# mcu.net
KiCad netlist of a schematic drawn in Altium Designer
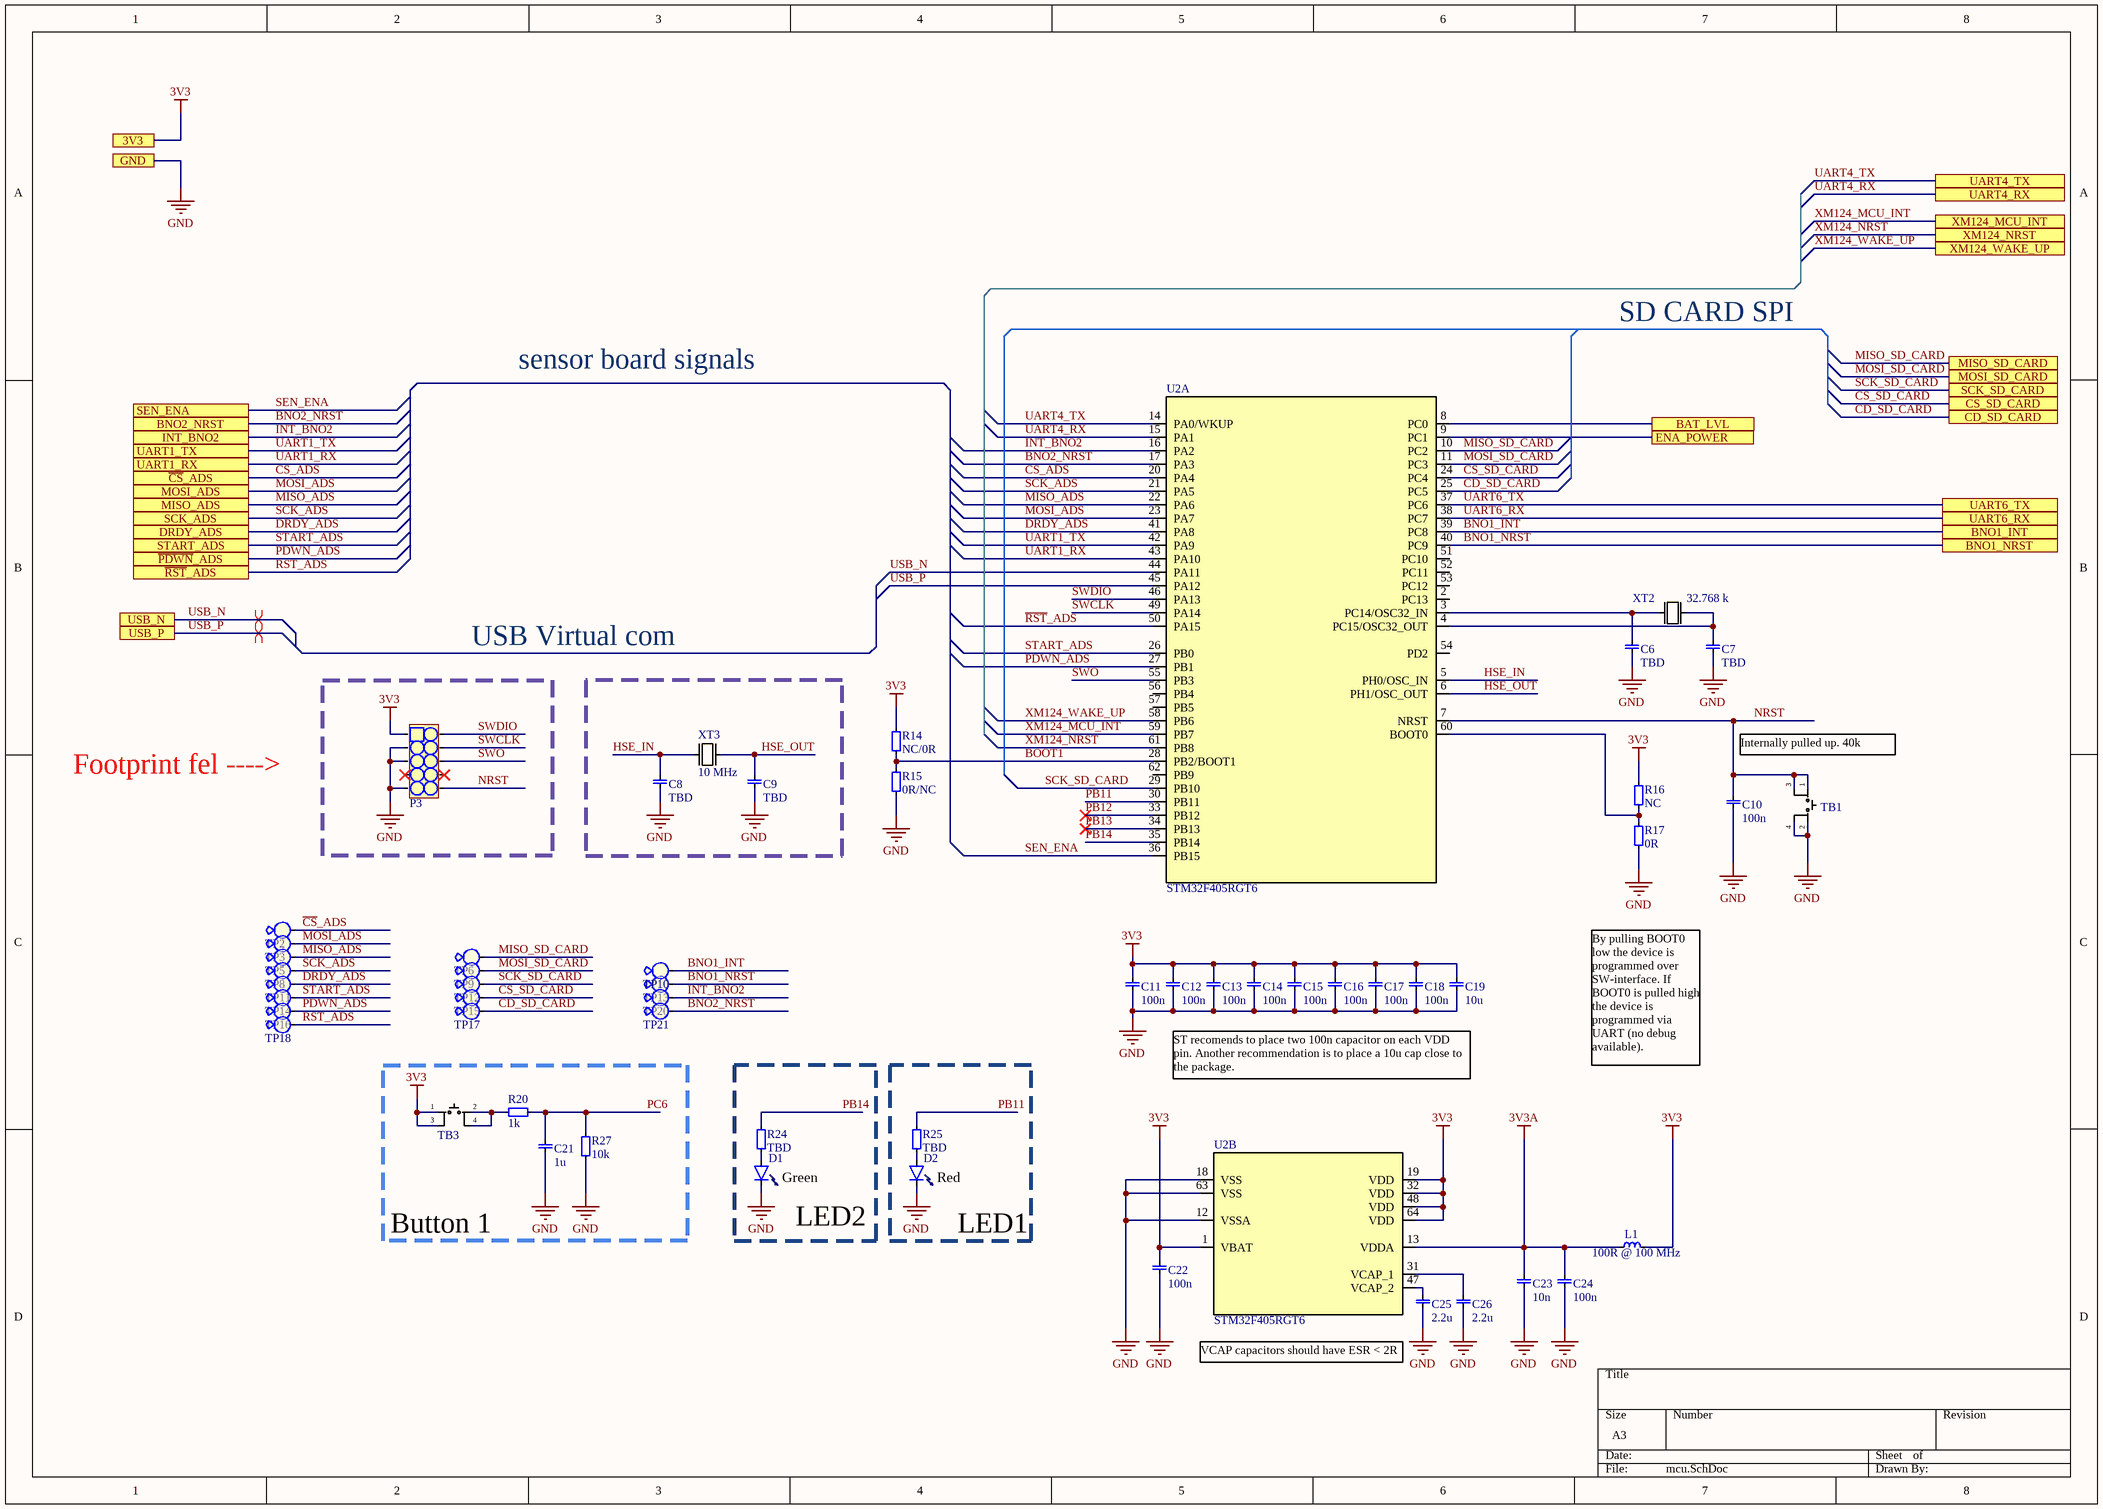
[diagram p0: mcu.SchDoc]

(export (version "E")
  (design (tool "Eeschema 10.0.6"))
  (components
    (comp (ref "C6")
      (value "TBD")
      (footprint "0603 cap")
      (fields (field (name "Comment") "0603, capacitor"))
      (libsource (lib "jclib") (part "0603, capacitor"))
    )
    (comp (ref "C7")
      (value "TBD")
      (footprint "0603 cap")
      (fields (field (name "Comment") "0603, capacitor"))
      (libsource (lib "jclib") (part "0603, capacitor"))
    )
    (comp (ref "C8")
      (value "TBD")
      (footprint "0603 cap")
      (fields (field (name "Comment") "0603, capacitor"))
      (libsource (lib "jclib") (part "0603, capacitor"))
    )
    (comp (ref "C9")
      (value "TBD")
      (footprint "0603 cap")
      (fields (field (name "Comment") "0603, capacitor"))
      (libsource (lib "jclib") (part "0603, capacitor"))
    )
    (comp (ref "C10")
      (value "100n")
      (footprint "0402 CAP")
      (fields
        (field (name "MANUFACTURER PART NO") "GRM155R62A104KE14D")
        (field (name "Comment") "0603, capacitor")
      )
      (libsource (lib "jclib") (part "0603, capacitor"))
    )
    (comp (ref "C11")
      (value "100n")
      (footprint "0402 CAP")
      (fields
        (field (name "MANUFACTURER PART NO") "GRM155R62A104KE14D")
        (field (name "Comment") "0603, capacitor")
      )
      (libsource (lib "jclib") (part "0603, capacitor"))
    )
    (comp (ref "C12")
      (value "100n")
      (footprint "0402 CAP")
      (fields
        (field (name "MANUFACTURER PART NO") "GRM155R62A104KE14D")
        (field (name "Comment") "0603, capacitor")
      )
      (libsource (lib "jclib") (part "0603, capacitor"))
    )
    (comp (ref "C13")
      (value "100n")
      (footprint "0402 CAP")
      (fields
        (field (name "MANUFACTURER PART NO") "GRM155R62A104KE14D")
        (field (name "Comment") "0603, capacitor")
      )
      (libsource (lib "jclib") (part "0603, capacitor"))
    )
    (comp (ref "C14")
      (value "100n")
      (footprint "0402 CAP")
      (fields
        (field (name "MANUFACTURER PART NO") "GRM155R62A104KE14D")
        (field (name "Comment") "0603, capacitor")
      )
      (libsource (lib "jclib") (part "0603, capacitor"))
    )
    (comp (ref "C15")
      (value "100n")
      (footprint "0402 CAP")
      (fields
        (field (name "MANUFACTURER PART NO") "GRM155R62A104KE14D")
        (field (name "Comment") "0603, capacitor")
      )
      (libsource (lib "jclib") (part "0603, capacitor"))
    )
    (comp (ref "C16")
      (value "100n")
      (footprint "0402 CAP")
      (fields
        (field (name "MANUFACTURER PART NO") "GRM155R62A104KE14D")
        (field (name "Comment") "0603, capacitor")
      )
      (libsource (lib "jclib") (part "0603, capacitor"))
    )
    (comp (ref "C17")
      (value "100n")
      (footprint "0402 CAP")
      (fields
        (field (name "MANUFACTURER PART NO") "GRM155R62A104KE14D")
        (field (name "Comment") "0603, capacitor")
      )
      (libsource (lib "jclib") (part "0603, capacitor"))
    )
    (comp (ref "C18")
      (value "100n")
      (footprint "0402 CAP")
      (fields
        (field (name "MANUFACTURER PART NO") "GRM155R62A104KE14D")
        (field (name "Comment") "0603, capacitor")
      )
      (libsource (lib "jclib") (part "0603, capacitor"))
    )
    (comp (ref "C19")
      (value "10u")
      (footprint "0402 CAP")
      (fields
        (field (name "MANUFACTURER PART NO") "GRM155R61A106ME11D")
        (field (name "Comment") "0603, capacitor")
      )
      (libsource (lib "jclib") (part "0603, capacitor"))
    )
    (comp (ref "C21")
      (value "1u")
      (footprint "0402 CAP")
      (fields
        (field (name "MANUFACTURER PART NO") "C0402C105K9PAC7867")
        (field (name "Comment") "0603, capacitor")
      )
      (libsource (lib "jclib") (part "0603, capacitor"))
    )
    (comp (ref "C22")
      (value "100n")
      (footprint "0402 CAP")
      (fields
        (field (name "MANUFACTURER PART NO") "GRM155R62A104KE14D")
        (field (name "Comment") "0603, capacitor")
      )
      (libsource (lib "jclib") (part "0603, capacitor"))
    )
    (comp (ref "C23")
      (value "10n")
      (footprint "0402 CAP")
      (fields
        (field (name "MANUFACTURER PART NO") "CC0402KRX7R0BB103")
        (field (name "Comment") "0603, capacitor")
      )
      (libsource (lib "jclib") (part "0603, capacitor"))
    )
    (comp (ref "C24")
      (value "100n")
      (footprint "0402 CAP")
      (fields
        (field (name "MANUFACTURER PART NO") "GRM155R62A104KE14D")
        (field (name "Comment") "0603, capacitor")
      )
      (libsource (lib "jclib") (part "0603, capacitor"))
    )
    (comp (ref "C25")
      (value "2.2u")
      (footprint "0402 CAP")
      (fields
        (field (name "MANUFACTURER PART NO") "GRM155D71A225ME15D")
        (field (name "Comment") "0603, capacitor")
      )
      (libsource (lib "jclib") (part "0603, capacitor"))
    )
    (comp (ref "C26")
      (value "2.2u")
      (footprint "0402 CAP")
      (fields
        (field (name "MANUFACTURER PART NO") "GRM155D71A225ME15D")
        (field (name "Comment") "0603, capacitor")
      )
      (libsource (lib "jclib") (part "0603, capacitor"))
    )
    (comp (ref "D1")
      (value "0603, LED")
      (footprint "0603 LED")
      (fields (field (name "MANUFACTURER PART NO") "5988081107F"))
      (libsource (lib "jclib") (part "0603, LED"))
    )
    (comp (ref "D2")
      (value "0603, LED")
      (footprint "0603 LED")
      (fields (field (name "MANUFACTURER PART NO") "150060SS75003"))
      (libsource (lib "jclib") (part "0603, LED"))
    )
    (comp (ref "L1")
      (value "100R @ 100 MHz")
      (footprint "0805")
      (fields (field (name "MANUFACTURER PART NO") "74279207") (field (name "Comment") "0805, Ferrite Bead"))
      (libsource (lib "jclib") (part "0805, Ferrite Bead"))
    )
    (comp (ref "P3")
      (value "ARM 10 pin SWD")
      (footprint "FTSH-105-01-L-DV-K even odd")
      (description "1.27mm, PH")
      (fields (field (name "MANUFACTURER PART NO") "FTSH-105-01-L-DV-K"))
      (libsource (lib "jclib") (part "ARM 10 pin SWD"))
    )
    (comp (ref "R14")
      (value "NC/0R")
      (footprint "0402 res")
      (fields
        (field (name "MANUFACTURER PART NO") "RMCF0402ZT0R00")
        (field (name "Comment") "0603, resistor")
      )
      (libsource (lib "jclib") (part "0603, resistor"))
    )
    (comp (ref "R15")
      (value "0R/NC")
      (footprint "0402 res")
      (fields
        (field (name "MANUFACTURER PART NO") "RMCF0402ZT0R00")
        (field (name "Comment") "0603, resistor")
      )
      (libsource (lib "jclib") (part "0603, resistor"))
    )
    (comp (ref "R16")
      (value "NC")
      (footprint "0402 res")
      (fields (field (name "Comment") "0603, resistor"))
      (libsource (lib "jclib") (part "0603, resistor"))
    )
    (comp (ref "R17")
      (value "0R")
      (footprint "0402 res")
      (fields
        (field (name "MANUFACTURER PART NO") "RMCF0402ZT0R00")
        (field (name "Comment") "0603, resistor")
      )
      (libsource (lib "jclib") (part "0603, resistor"))
    )
    (comp (ref "R20")
      (value "1k")
      (footprint "0402 res")
      (fields
        (field (name "MANUFACTURER PART NO") "RC0402FR-071KL")
        (field (name "Comment") "0603, resistor")
      )
      (libsource (lib "jclib") (part "0603, resistor"))
    )
    (comp (ref "R24")
      (value "TBD")
      (footprint "0402 res")
      (fields (field (name "Comment") "0603, resistor"))
      (libsource (lib "jclib") (part "0603, resistor"))
    )
    (comp (ref "R25")
      (value "TBD")
      (footprint "0402 res")
      (fields (field (name "Comment") "0603, resistor"))
      (libsource (lib "jclib") (part "0603, resistor"))
    )
    (comp (ref "R27")
      (value "10k")
      (footprint "0402 res")
      (fields
        (field (name "MANUFACTURER PART NO") "311-10.0KLRCT-ND")
        (field (name "Comment") "0603, resistor")
      )
      (libsource (lib "jclib") (part "0603, resistor"))
    )
    (comp (ref "TB1")
      (value "Tactile Button")
      (footprint "tacButton smd")
      (description "Tactile Switch Small Low")
      (fields (field (name "MANUFACTURER PART NO") "430182043816"))
      (libsource (lib "jclib") (part "TacButton SMD"))
    )
    (comp (ref "TB3")
      (value "Tactile Button")
      (footprint "tacButton smd")
      (description "Tactile Switch Small Low")
      (fields (field (name "MANUFACTURER PART NO") "430182043816"))
      (libsource (lib "jclib") (part "TacButton SMD"))
    )
    (comp (ref "TP2")
      (value "Test Point")
      (footprint "testPoint")
      (libsource (lib "jclib") (part "Test Point"))
    )
    (comp (ref "TP3")
      (value "Test Point")
      (footprint "testPoint")
      (libsource (lib "jclib") (part "Test Point"))
    )
    (comp (ref "TP5")
      (value "Test Point")
      (footprint "testPoint")
      (libsource (lib "jclib") (part "Test Point"))
    )
    (comp (ref "TP6")
      (value "Test Point")
      (footprint "testPoint")
      (libsource (lib "jclib") (part "Test Point"))
    )
    (comp (ref "TP8")
      (value "Test Point")
      (footprint "testPoint")
      (libsource (lib "jclib") (part "Test Point"))
    )
    (comp (ref "TP9")
      (value "Test Point")
      (footprint "testPoint")
      (libsource (lib "jclib") (part "Test Point"))
    )
    (comp (ref "TP10")
      (value "Test Point")
      (footprint "testPoint")
      (libsource (lib "jclib") (part "Test Point"))
    )
    (comp (ref "TP11")
      (value "Test Point")
      (footprint "testPoint")
      (libsource (lib "jclib") (part "Test Point"))
    )
    (comp (ref "TP12")
      (value "Test Point")
      (footprint "testPoint")
      (libsource (lib "jclib") (part "Test Point"))
    )
    (comp (ref "TP13")
      (value "Test Point")
      (footprint "testPoint")
      (libsource (lib "jclib") (part "Test Point"))
    )
    (comp (ref "TP14")
      (value "Test Point")
      (footprint "testPoint")
      (libsource (lib "jclib") (part "Test Point"))
    )
    (comp (ref "TP15")
      (value "Test Point")
      (footprint "testPoint")
      (libsource (lib "jclib") (part "Test Point"))
    )
    (comp (ref "TP16")
      (value "Test Point")
      (footprint "testPoint")
      (libsource (lib "jclib") (part "Test Point"))
    )
    (comp (ref "TP17")
      (value "Test Point")
      (footprint "testPoint")
      (libsource (lib "jclib") (part "Test Point"))
    )
    (comp (ref "TP18")
      (value "Test Point")
      (footprint "testPoint")
      (libsource (lib "jclib") (part "Test Point"))
    )
    (comp (ref "TP20")
      (value "Test Point")
      (footprint "testPoint")
      (libsource (lib "jclib") (part "Test Point"))
    )
    (comp (ref "TP21")
      (value "Test Point")
      (footprint "testPoint")
      (libsource (lib "jclib") (part "Test Point"))
    )
    (comp (ref "U2")
      (value "STM32F405RGT6")
      (footprint "LQFP64-10x10mm_s")
      (description "No Description Available")
      (fields (field (name "COPYRIGHT") "Copyright (C) 2018 Accelerated Designs. All rights reserved"))
      (libsource (lib "jclib") (part "STM32F405RGT6"))
    )
    (comp (ref "XT2")
      (value "32.768 k")
      (footprint "ECS-.327-12.5-39-TR")
      (fields
        (field (name "MANUFACTURER PART NO") "CC4V-T1A-32.768KHZ-9PF-20PPM-TA-QC")
        (field (name "Comment") "Crystal")
      )
      (libsource (lib "jclib") (part "Crystal"))
    )
    (comp (ref "XT3")
      (value "10 MHz")
      (footprint "XTAL_SMD_LP")
      (description "16 MHz, SMD, 5mm x 3,2mm, 30 ppm")
      (fields (field (name "MANUFACTURER PART NO") "7A-10.000MAAJ-T") (field (name "Comment") "XTAL TXC 7A"))
      (libsource (lib "jclib") (part "XTAL TXC 7A"))
    )
  )
  (nets
    (net (code "1") (name "/BAT_LVL") (class "Default")
      (node (ref "U2") (pin "8") (pinfunction "PC0_8") (pintype "passive"))
    )
    (net (code "2") (name "/BNO1_INT") (class "Default")
      (node (ref "TP10") (pin "0") (pinfunction "0_0") (pintype "passive"))
      (node (ref "U2") (pin "39") (pinfunction "PC8_39") (pintype "passive"))
    )
    (net (code "3") (name "/BNO1_NRST") (class "Default")
      (node (ref "TP13") (pin "0") (pinfunction "0_0") (pintype "passive"))
      (node (ref "U2") (pin "40") (pinfunction "PC9_40") (pintype "passive"))
    )
    (net (code "4") (name "/BNO2_NRST") (class "Default")
      (node (ref "TP21") (pin "0") (pinfunction "0_0") (pintype "passive"))
      (node (ref "U2") (pin "17") (pinfunction "PA3_17") (pintype "passive"))
    )
    (net (code "5") (name "/BOOT1") (class "Default")
      (node (ref "R14") (pin "1") (pinfunction "1_1") (pintype "passive"))
      (node (ref "R15") (pin "0") (pinfunction "0_0") (pintype "passive"))
      (node (ref "U2") (pin "28") (pinfunction "PB2/BOOT1_28") (pintype "passive"))
    )
    (net (code "6") (name "/CD_SD_CARD") (class "Default")
      (node (ref "TP17") (pin "0") (pinfunction "0_0") (pintype "passive"))
      (node (ref "U2") (pin "25") (pinfunction "PC5_25") (pintype "passive"))
    )
    (net (code "7") (name "/CS_SD_CARD") (class "Default")
      (node (ref "TP15") (pin "0") (pinfunction "0_0") (pintype "passive"))
      (node (ref "U2") (pin "24") (pinfunction "PC4_24") (pintype "passive"))
    )
    (net (code "8") (name "/DRDY_ADS") (class "Default")
      (node (ref "TP11") (pin "0") (pinfunction "0_0") (pintype "passive"))
      (node (ref "U2") (pin "41") (pinfunction "PA8_41") (pintype "passive"))
    )
    (net (code "9") (name "/ENA_POWER") (class "Default")
      (node (ref "U2") (pin "9") (pinfunction "PC1_9") (pintype "passive"))
    )
    (net (code "10") (name "/HSE_IN") (class "Default")
      (node (ref "C8") (pin "1") (pinfunction "1_1") (pintype "passive"))
      (node (ref "U2") (pin "5") (pinfunction "PH0/OSC_IN_5") (pintype "passive"))
      (node (ref "XT3") (pin "1") (pinfunction "1_1") (pintype "passive"))
    )
    (net (code "11") (name "/HSE_OUT") (class "Default")
      (node (ref "C9") (pin "1") (pinfunction "1_1") (pintype "passive"))
      (node (ref "U2") (pin "6") (pinfunction "PH1/OSC_OUT_6") (pintype "passive"))
      (node (ref "XT3") (pin "2") (pinfunction "2_2") (pintype "passive"))
    )
    (net (code "12") (name "/INT_BNO2") (class "Default")
      (node (ref "TP20") (pin "0") (pinfunction "0_0") (pintype "passive"))
      (node (ref "U2") (pin "16") (pinfunction "PA2_16") (pintype "passive"))
    )
    (net (code "13") (name "/MISO_ADS") (class "Default")
      (node (ref "TP5") (pin "0") (pinfunction "0_0") (pintype "passive"))
      (node (ref "U2") (pin "22") (pinfunction "PA6_22") (pintype "passive"))
    )
    (net (code "14") (name "/MISO_SD_CARD") (class "Default")
      (node (ref "TP6") (pin "0") (pinfunction "0_0") (pintype "passive"))
      (node (ref "U2") (pin "10") (pinfunction "PC2_10") (pintype "passive"))
    )
    (net (code "15") (name "/MOSI_ADS") (class "Default")
      (node (ref "TP3") (pin "0") (pinfunction "0_0") (pintype "passive"))
      (node (ref "U2") (pin "23") (pinfunction "PA7_23") (pintype "passive"))
    )
    (net (code "16") (name "/MOSI_SD_CARD") (class "Default")
      (node (ref "TP9") (pin "0") (pinfunction "0_0") (pintype "passive"))
      (node (ref "U2") (pin "11") (pinfunction "PC3_11") (pintype "passive"))
    )
    (net (code "17") (name "/NRST") (class "Default")
      (node (ref "C10") (pin "1") (pinfunction "1_1") (pintype "passive"))
      (node (ref "P3") (pin "10") (pinfunction "10_10") (pintype "passive"))
      (node (ref "TB1") (pin "1") (pinfunction "1_1") (pintype "passive"))
      (node (ref "TB1") (pin "3") (pinfunction "3_3") (pintype "passive"))
      (node (ref "U2") (pin "7") (pinfunction "NRST_7") (pintype "passive"))
    )
    (net (code "18") (name "/PB11") (class "Default")
      (node (ref "R25") (pin "1") (pinfunction "1_1") (pintype "passive"))
      (node (ref "U2") (pin "30") (pinfunction "PB11_30") (pintype "passive"))
    )
    (net (code "19") (name "/PB12") (class "Default")
      (node (ref "U2") (pin "33") (pinfunction "PB12_33") (pintype "passive+no_connect"))
    )
    (net (code "20") (name "/PB13") (class "Default")
      (node (ref "U2") (pin "34") (pinfunction "PB13_34") (pintype "passive+no_connect"))
    )
    (net (code "21") (name "/PB14") (class "Default")
      (node (ref "R24") (pin "1") (pinfunction "1_1") (pintype "passive"))
      (node (ref "U2") (pin "35") (pinfunction "PB14_35") (pintype "passive"))
    )
    (net (code "22") (name "/PC6") (class "Default")
      (node (ref "C21") (pin "1") (pinfunction "1_1") (pintype "passive"))
      (node (ref "R20") (pin "1") (pinfunction "1_1") (pintype "passive"))
      (node (ref "R27") (pin "1") (pinfunction "1_1") (pintype "passive"))
    )
    (net (code "23") (name "/SCK_ADS") (class "Default")
      (node (ref "TP8") (pin "0") (pinfunction "0_0") (pintype "passive"))
      (node (ref "U2") (pin "21") (pinfunction "PA5_21") (pintype "passive"))
    )
    (net (code "24") (name "/SCK_SD_CARD") (class "Default")
      (node (ref "TP12") (pin "0") (pinfunction "0_0") (pintype "passive"))
      (node (ref "U2") (pin "29") (pinfunction "PB10_29") (pintype "passive"))
    )
    (net (code "25") (name "/SEN_ENA") (class "Default")
      (node (ref "U2") (pin "36") (pinfunction "PB15_36") (pintype "passive"))
    )
    (net (code "26") (name "/START_ADS") (class "Default")
      (node (ref "TP14") (pin "0") (pinfunction "0_0") (pintype "passive"))
      (node (ref "U2") (pin "26") (pinfunction "PB0_26") (pintype "passive"))
    )
    (net (code "27") (name "/SWCLK") (class "Default")
      (node (ref "P3") (pin "4") (pinfunction "4_4") (pintype "passive"))
      (node (ref "U2") (pin "49") (pinfunction "PA14_49") (pintype "passive"))
    )
    (net (code "28") (name "/SWDIO") (class "Default")
      (node (ref "P3") (pin "2") (pinfunction "2_2") (pintype "passive"))
      (node (ref "U2") (pin "46") (pinfunction "PA13_46") (pintype "passive"))
    )
    (net (code "29") (name "/SWO") (class "Default")
      (node (ref "P3") (pin "6") (pinfunction "6_6") (pintype "passive"))
      (node (ref "U2") (pin "55") (pinfunction "PB3_55") (pintype "passive"))
    )
    (net (code "30") (name "/UART1_RX") (class "Default")
      (node (ref "U2") (pin "43") (pinfunction "PA10_43") (pintype "passive"))
    )
    (net (code "31") (name "/UART1_TX") (class "Default")
      (node (ref "U2") (pin "42") (pinfunction "PA9_42") (pintype "passive"))
    )
    (net (code "32") (name "/UART4_RX") (class "Default")
      (node (ref "U2") (pin "15") (pinfunction "PA1_15") (pintype "passive"))
    )
    (net (code "33") (name "/UART4_TX") (class "Default")
      (node (ref "U2") (pin "14") (pinfunction "PA0/WKUP_14") (pintype "passive"))
    )
    (net (code "34") (name "/UART6_RX") (class "Default")
      (node (ref "U2") (pin "38") (pinfunction "PC7_38") (pintype "passive"))
    )
    (net (code "35") (name "/UART6_TX") (class "Default")
      (node (ref "U2") (pin "37") (pinfunction "PC6_37") (pintype "passive"))
    )
    (net (code "36") (name "/USB_N") (class "Default")
      (node (ref "U2") (pin "44") (pinfunction "PA11_44") (pintype "passive"))
    )
    (net (code "37") (name "/USB_P") (class "Default")
      (node (ref "U2") (pin "45") (pinfunction "PA12_45") (pintype "passive"))
    )
    (net (code "38") (name "/XM124_MCU_INT") (class "Default")
      (node (ref "U2") (pin "59") (pinfunction "PB7_59") (pintype "passive"))
    )
    (net (code "39") (name "/XM124_NRST") (class "Default")
      (node (ref "U2") (pin "61") (pinfunction "PB8_61") (pintype "passive"))
    )
    (net (code "40") (name "/XM124_WAKE_UP") (class "Default")
      (node (ref "U2") (pin "58") (pinfunction "PB6_58") (pintype "passive"))
    )
    (net (code "41") (name "/~{CS}_ADS") (class "Default")
      (node (ref "TP2") (pin "0") (pinfunction "0_0") (pintype "passive"))
      (node (ref "U2") (pin "20") (pinfunction "PA4_20") (pintype "passive"))
    )
    (net (code "42") (name "/~{PDWN}_ADS") (class "Default")
      (node (ref "TP16") (pin "0") (pinfunction "0_0") (pintype "passive"))
      (node (ref "U2") (pin "27") (pinfunction "PB1_27") (pintype "passive"))
    )
    (net (code "43") (name "/~{RST}_ADS") (class "Default")
      (node (ref "TP18") (pin "0") (pinfunction "0_0") (pintype "passive"))
      (node (ref "U2") (pin "50") (pinfunction "PA15_50") (pintype "passive"))
    )
    (net (code "44") (name "3V3") (class "Default")
      (node (ref "C11") (pin "1") (pinfunction "1_1") (pintype "passive"))
      (node (ref "C12") (pin "1") (pinfunction "1_1") (pintype "passive"))
      (node (ref "C13") (pin "1") (pinfunction "1_1") (pintype "passive"))
      (node (ref "C14") (pin "1") (pinfunction "1_1") (pintype "passive"))
      (node (ref "C15") (pin "1") (pinfunction "1_1") (pintype "passive"))
      (node (ref "C16") (pin "1") (pinfunction "1_1") (pintype "passive"))
      (node (ref "C17") (pin "1") (pinfunction "1_1") (pintype "passive"))
      (node (ref "C18") (pin "1") (pinfunction "1_1") (pintype "passive"))
      (node (ref "C19") (pin "1") (pinfunction "1_1") (pintype "passive"))
      (node (ref "C22") (pin "1") (pinfunction "1_1") (pintype "passive"))
      (node (ref "L1") (pin "0") (pinfunction "0_0") (pintype "passive"))
      (node (ref "P3") (pin "1") (pinfunction "1_1") (pintype "passive"))
      (node (ref "R14") (pin "0") (pinfunction "0_0") (pintype "passive"))
      (node (ref "R16") (pin "0") (pinfunction "0_0") (pintype "passive"))
      (node (ref "TB3") (pin "1") (pinfunction "1_1") (pintype "passive"))
      (node (ref "TB3") (pin "3") (pinfunction "3_3") (pintype "passive"))
      (node (ref "U2") (pin "1") (pinfunction "VBAT_1") (pintype "power_in"))
      (node (ref "U2") (pin "19") (pinfunction "VDD_19") (pintype "power_in"))
      (node (ref "U2") (pin "32") (pinfunction "VDD_32") (pintype "power_in"))
      (node (ref "U2") (pin "48") (pinfunction "VDD_48") (pintype "power_in"))
      (node (ref "U2") (pin "64") (pinfunction "VDD_64") (pintype "power_in"))
    )
    (net (code "45") (name "3V3A") (class "Default")
      (node (ref "C23") (pin "1") (pinfunction "1_1") (pintype "passive"))
      (node (ref "C24") (pin "1") (pinfunction "1_1") (pintype "passive"))
      (node (ref "L1") (pin "1") (pinfunction "1_1") (pintype "passive"))
      (node (ref "U2") (pin "13") (pinfunction "VDDA_13") (pintype "power_in"))
    )
    (net (code "46") (name "GND") (class "Default")
      (node (ref "C10") (pin "0") (pinfunction "0_0") (pintype "passive"))
      (node (ref "C11") (pin "0") (pinfunction "0_0") (pintype "passive"))
      (node (ref "C12") (pin "0") (pinfunction "0_0") (pintype "passive"))
      (node (ref "C13") (pin "0") (pinfunction "0_0") (pintype "passive"))
      (node (ref "C14") (pin "0") (pinfunction "0_0") (pintype "passive"))
      (node (ref "C15") (pin "0") (pinfunction "0_0") (pintype "passive"))
      (node (ref "C16") (pin "0") (pinfunction "0_0") (pintype "passive"))
      (node (ref "C17") (pin "0") (pinfunction "0_0") (pintype "passive"))
      (node (ref "C18") (pin "0") (pinfunction "0_0") (pintype "passive"))
      (node (ref "C19") (pin "0") (pinfunction "0_0") (pintype "passive"))
      (node (ref "C21") (pin "0") (pinfunction "0_0") (pintype "passive"))
      (node (ref "C22") (pin "0") (pinfunction "0_0") (pintype "passive"))
      (node (ref "C23") (pin "0") (pinfunction "0_0") (pintype "passive"))
      (node (ref "C24") (pin "0") (pinfunction "0_0") (pintype "passive"))
      (node (ref "C25") (pin "0") (pinfunction "0_0") (pintype "passive"))
      (node (ref "C26") (pin "0") (pinfunction "0_0") (pintype "passive"))
      (node (ref "C6") (pin "0") (pinfunction "0_0") (pintype "passive"))
      (node (ref "C7") (pin "0") (pinfunction "0_0") (pintype "passive"))
      (node (ref "C8") (pin "0") (pinfunction "0_0") (pintype "passive"))
      (node (ref "C9") (pin "0") (pinfunction "0_0") (pintype "passive"))
      (node (ref "D1") (pin "0") (pinfunction "Cathode_0") (pintype "passive"))
      (node (ref "D2") (pin "0") (pinfunction "Cathode_0") (pintype "passive"))
      (node (ref "P3") (pin "3") (pinfunction "3_3") (pintype "passive"))
      (node (ref "P3") (pin "5") (pinfunction "5_5") (pintype "passive"))
      (node (ref "P3") (pin "9") (pinfunction "9_9") (pintype "passive"))
      (node (ref "R15") (pin "1") (pinfunction "1_1") (pintype "passive"))
      (node (ref "R17") (pin "1") (pinfunction "1_1") (pintype "passive"))
      (node (ref "R27") (pin "0") (pinfunction "0_0") (pintype "passive"))
      (node (ref "TB1") (pin "2") (pinfunction "2_2") (pintype "passive"))
      (node (ref "TB1") (pin "4") (pinfunction "4_4") (pintype "passive"))
      (node (ref "U2") (pin "12") (pinfunction "VSSA_12") (pintype "power_in"))
      (node (ref "U2") (pin "18") (pinfunction "VSS_18") (pintype "power_in"))
      (node (ref "U2") (pin "63") (pinfunction "VSS_63") (pintype "power_in"))
    )
    (net (code "47") (name "Net-(D1-Pad1)") (class "Default")
      (node (ref "D1") (pin "1") (pinfunction "1_1") (pintype "passive"))
      (node (ref "R24") (pin "0") (pinfunction "0_0") (pintype "passive"))
    )
    (net (code "48") (name "Net-(D2-Pad1)") (class "Default")
      (node (ref "D2") (pin "1") (pinfunction "1_1") (pintype "passive"))
      (node (ref "R25") (pin "0") (pinfunction "0_0") (pintype "passive"))
    )
    (net (code "49") (name "Net-(R20-Pad0)") (class "Default")
      (node (ref "R20") (pin "0") (pinfunction "0_0") (pintype "passive"))
      (node (ref "TB3") (pin "2") (pinfunction "2_2") (pintype "passive"))
      (node (ref "TB3") (pin "4") (pinfunction "4_4") (pintype "passive"))
    )
    (net (code "50") (name "Net-(U2A-BOOT0)") (class "Default")
      (node (ref "R16") (pin "1") (pinfunction "1_1") (pintype "passive"))
      (node (ref "R17") (pin "0") (pinfunction "0_0") (pintype "passive"))
      (node (ref "U2") (pin "60") (pinfunction "BOOT0_60") (pintype "passive"))
    )
    (net (code "51") (name "Net-(U2A-PC14{slash}OSC32_IN)") (class "Default")
      (node (ref "C6") (pin "1") (pinfunction "1_1") (pintype "passive"))
      (node (ref "U2") (pin "3") (pinfunction "PC14/OSC32_IN_3") (pintype "passive"))
      (node (ref "XT2") (pin "1") (pinfunction "1_1") (pintype "passive"))
    )
    (net (code "52") (name "Net-(U2A-PC15{slash}OSC32_OUT)") (class "Default")
      (node (ref "C7") (pin "1") (pinfunction "1_1") (pintype "passive"))
      (node (ref "U2") (pin "4") (pinfunction "PC15/OSC32_OUT_4") (pintype "passive"))
      (node (ref "XT2") (pin "2") (pinfunction "2_2") (pintype "passive"))
    )
    (net (code "53") (name "Net-(U2B-VCAP_1)") (class "Default")
      (node (ref "C26") (pin "1") (pinfunction "1_1") (pintype "passive"))
      (node (ref "U2") (pin "31") (pinfunction "VCAP_1_31") (pintype "power_in"))
    )
    (net (code "54") (name "Net-(U2B-VCAP_2)") (class "Default")
      (node (ref "C25") (pin "1") (pinfunction "1_1") (pintype "passive"))
      (node (ref "U2") (pin "47") (pinfunction "VCAP_2_47") (pintype "power_in"))
    )
    (net (code "55") (name "unconnected-(P3-Pad7)") (class "Default")
      (node (ref "P3") (pin "7") (pinfunction "7_7") (pintype "passive+no_connect"))
    )
    (net (code "56") (name "unconnected-(P3-Pad8)") (class "Default")
      (node (ref "P3") (pin "8") (pinfunction "8_8") (pintype "passive+no_connect"))
    )
    (net (code "57") (name "unconnected-(U2A-PB4-Pad56)") (class "Default")
      (node (ref "U2") (pin "56") (pinfunction "PB4_56") (pintype "passive"))
    )
    (net (code "58") (name "unconnected-(U2A-PB5-Pad57)") (class "Default")
      (node (ref "U2") (pin "57") (pinfunction "PB5_57") (pintype "passive"))
    )
    (net (code "59") (name "unconnected-(U2A-PB9-Pad62)") (class "Default")
      (node (ref "U2") (pin "62") (pinfunction "PB9_62") (pintype "passive"))
    )
    (net (code "60") (name "unconnected-(U2A-PC10-Pad51)") (class "Default")
      (node (ref "U2") (pin "51") (pinfunction "PC10_51") (pintype "passive"))
    )
    (net (code "61") (name "unconnected-(U2A-PC11-Pad52)") (class "Default")
      (node (ref "U2") (pin "52") (pinfunction "PC11_52") (pintype "passive"))
    )
    (net (code "62") (name "unconnected-(U2A-PC12-Pad53)") (class "Default")
      (node (ref "U2") (pin "53") (pinfunction "PC12_53") (pintype "passive"))
    )
    (net (code "63") (name "unconnected-(U2A-PC13-Pad2)") (class "Default")
      (node (ref "U2") (pin "2") (pinfunction "PC13_2") (pintype "passive"))
    )
    (net (code "64") (name "unconnected-(U2A-PD2-Pad54)") (class "Default")
      (node (ref "U2") (pin "54") (pinfunction "PD2_54") (pintype "passive"))
    )
  )
)
